# BaseTag.net
KiCad netlist of a schematic drawn in EAGLE
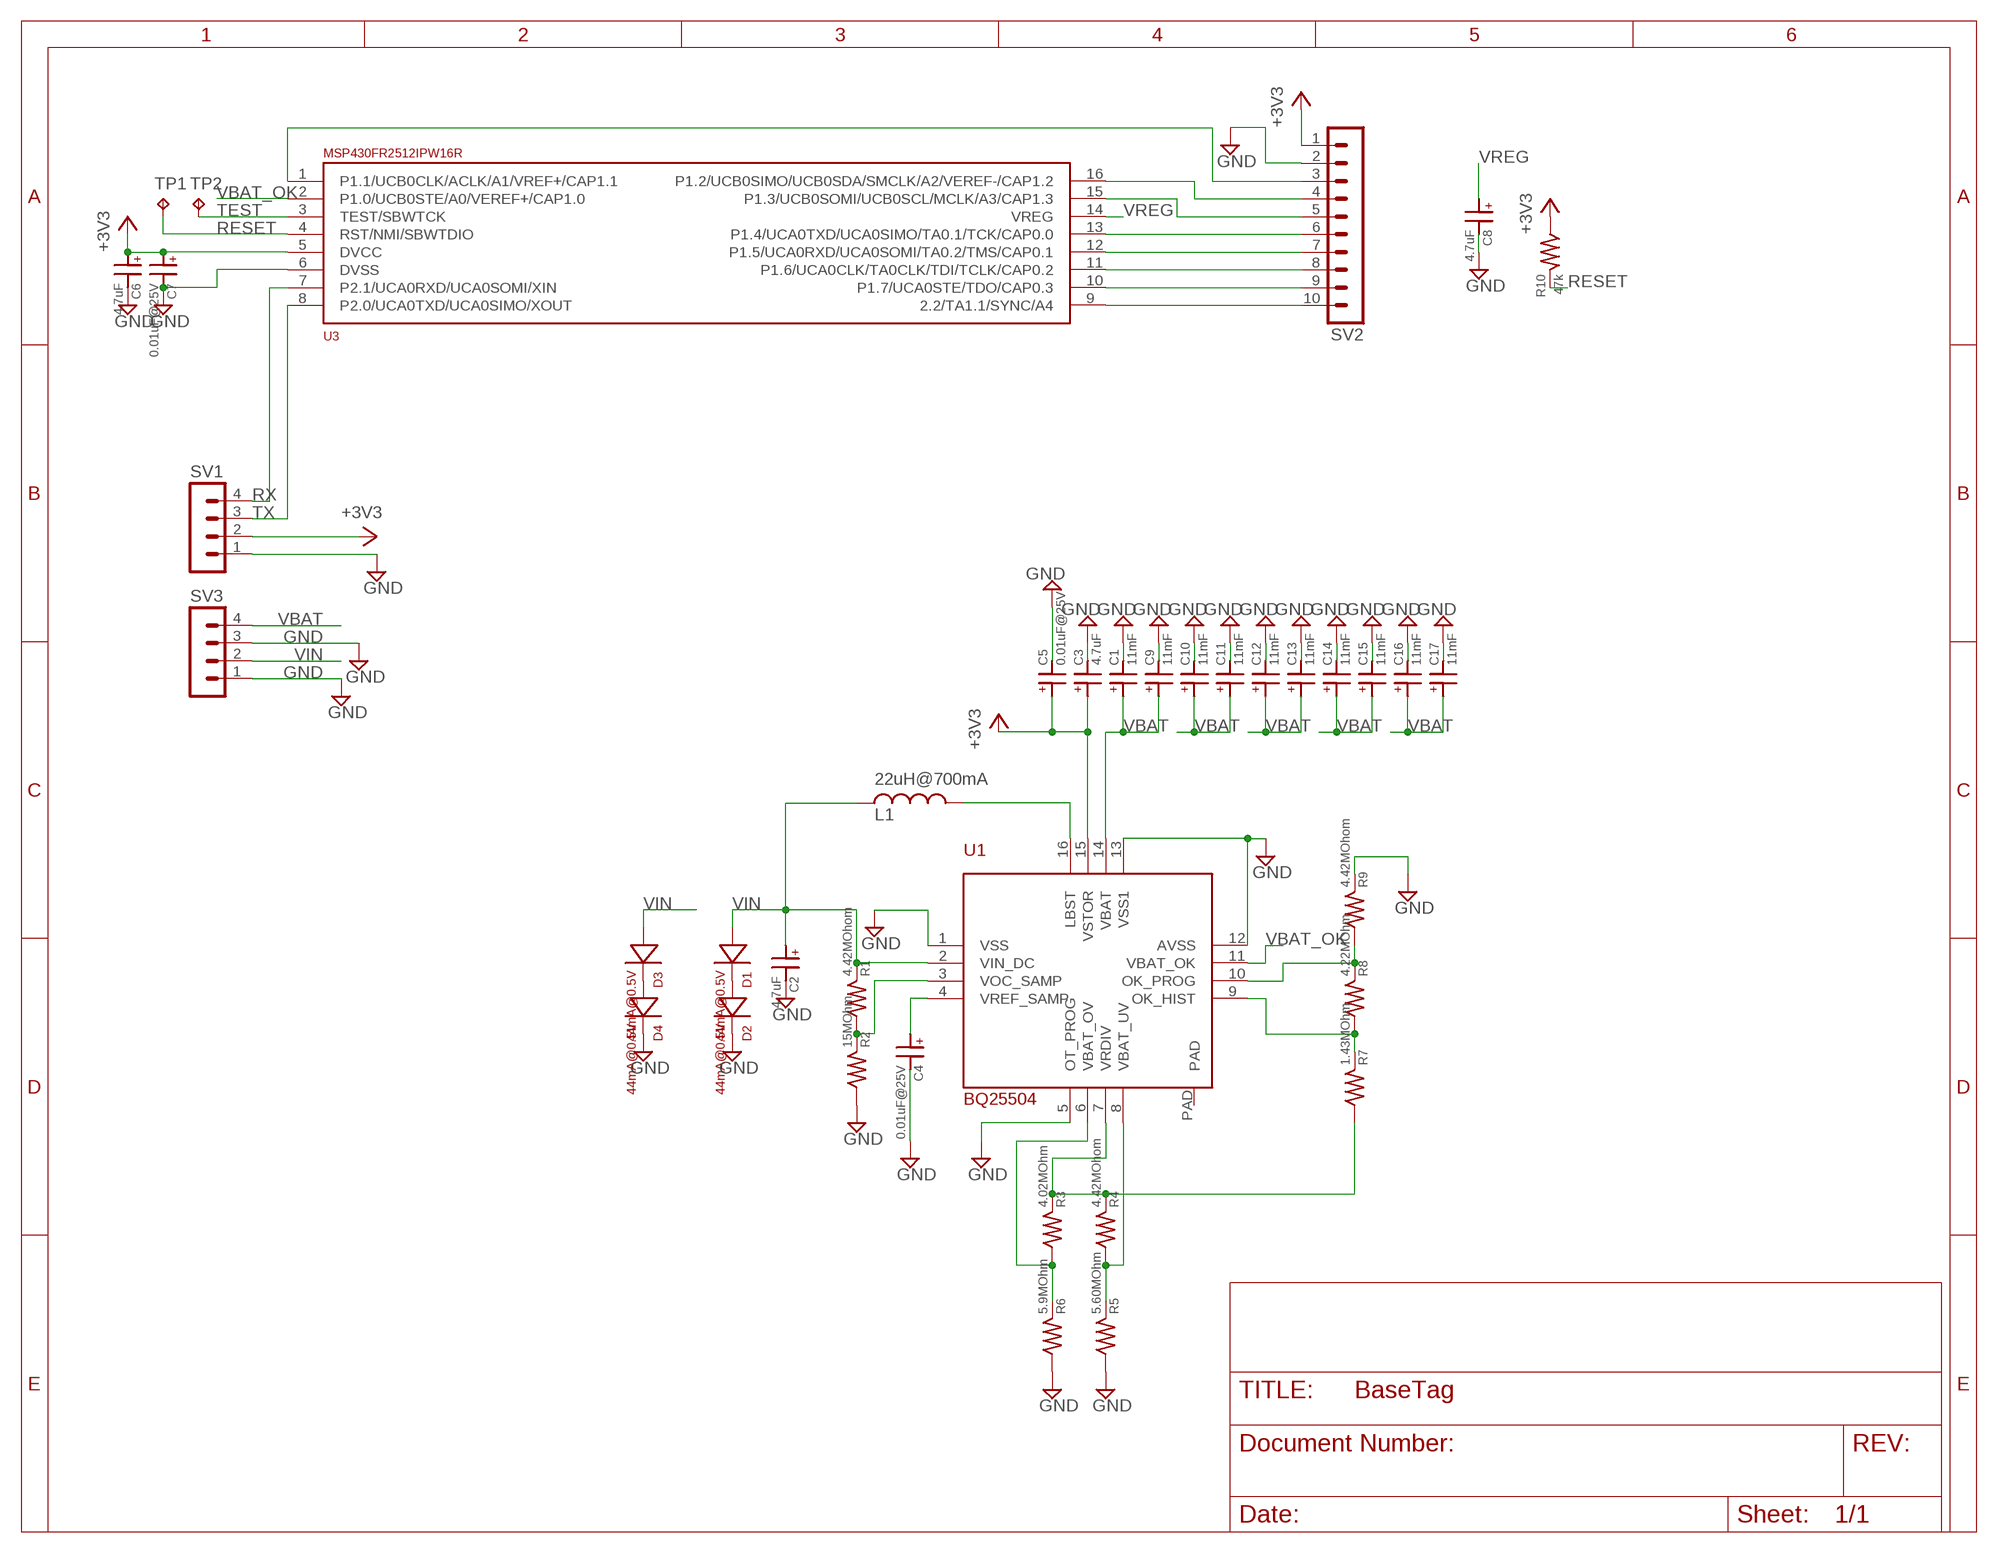
[diagram p0: schematic, sheet 1]

(export (version "E")
  (design (tool "Eeschema 10.0.6"))
  (components
    (comp (ref "C1")
      (value "11mF")
      (footprint "eagle-import:CPH3225A-2K")
      (fields (field (name "MFG") "Seiko Instruments ") (field (name "MPN") " CPH3225A-2K "))
      (libsource (lib "eagle-import") (part "Nelson-RLCD_4387371_C"))
    )
    (comp (ref "C2")
      (value "4.7uF")
      (footprint "eagle-import:0603")
      (fields (field (name "MFG") "Samsung") (field (name "MPN") "CL10A475MP5LNNC"))
      (libsource (lib "eagle-import") (part "C06034.7UF"))
    )
    (comp (ref "C3")
      (value "4.7uF")
      (footprint "eagle-import:0603")
      (fields (field (name "MFG") "Samsung") (field (name "MPN") "CL10A475MP5LNNC"))
      (libsource (lib "eagle-import") (part "Nelson-RLCD_4387371_C06034.7UF"))
    )
    (comp (ref "C4")
      (value "0.01uF@25V")
      (footprint "eagle-import:0603")
      (fields (field (name "MFG") "TDK") (field (name "MPN") "C1608C0G1E103J080AA"))
      (libsource (lib "eagle-import") (part "Nelson-RLCD_4387371_C06030.01UF"))
    )
    (comp (ref "C5")
      (value "0.01uF@25V")
      (footprint "eagle-import:0603")
      (fields (field (name "MFG") "TDK") (field (name "MPN") "C1608C0G1E103J080AA"))
      (libsource (lib "eagle-import") (part "Nelson-RLCD_4387371_C06030.01UF"))
    )
    (comp (ref "C6")
      (value "4.7uF")
      (footprint "eagle-import:0603")
      (fields (field (name "MFG") "Samsung") (field (name "MPN") "CL10A475MP5LNNC"))
      (libsource (lib "eagle-import") (part "Nelson-RLCD_4387371_C06034.7UF"))
    )
    (comp (ref "C7")
      (value "0.01uF@25V")
      (footprint "eagle-import:0603")
      (fields (field (name "MFG") "TDK") (field (name "MPN") "C1608C0G1E103J080AA"))
      (libsource (lib "eagle-import") (part "Nelson-RLCD_4387371_C06030.01UF"))
    )
    (comp (ref "C8")
      (value "4.7uF")
      (footprint "eagle-import:0603")
      (fields (field (name "MFG") "Samsung") (field (name "MPN") "CL10A475MP5LNNC"))
      (libsource (lib "eagle-import") (part "Nelson-RLCD_4387371_C06034.7UF"))
    )
    (comp (ref "C9")
      (value "11mF")
      (footprint "eagle-import:CPH3225A-2K")
      (fields (field (name "MFG") "Seiko Instruments ") (field (name "MPN") " CPH3225A-2K "))
      (libsource (lib "eagle-import") (part "Nelson-RLCD_4387371_C"))
    )
    (comp (ref "C10")
      (value "11mF")
      (footprint "eagle-import:CPH3225A-2K")
      (fields (field (name "MFG") "Seiko Instruments ") (field (name "MPN") " CPH3225A-2K "))
      (libsource (lib "eagle-import") (part "Nelson-RLCD_4387371_C"))
    )
    (comp (ref "C11")
      (value "11mF")
      (footprint "eagle-import:CPH3225A-2K")
      (fields (field (name "MFG") "Seiko Instruments ") (field (name "MPN") " CPH3225A-2K "))
      (libsource (lib "eagle-import") (part "C"))
    )
    (comp (ref "C12")
      (value "11mF")
      (footprint "eagle-import:CPH3225A-2K")
      (fields (field (name "MFG") "Seiko Instruments ") (field (name "MPN") " CPH3225A-2K "))
      (libsource (lib "eagle-import") (part "C"))
    )
    (comp (ref "C13")
      (value "11mF")
      (footprint "eagle-import:CPH3225A-2K")
      (fields (field (name "MFG") "Seiko Instruments ") (field (name "MPN") " CPH3225A-2K "))
      (libsource (lib "eagle-import") (part "C"))
    )
    (comp (ref "C14")
      (value "11mF")
      (footprint "eagle-import:CPH3225A-2K")
      (fields (field (name "MFG") "Seiko Instruments ") (field (name "MPN") " CPH3225A-2K "))
      (libsource (lib "eagle-import") (part "C"))
    )
    (comp (ref "C15")
      (value "11mF")
      (footprint "eagle-import:CPH3225A-2K")
      (fields (field (name "MFG") "Seiko Instruments ") (field (name "MPN") " CPH3225A-2K "))
      (libsource (lib "eagle-import") (part "C"))
    )
    (comp (ref "C16")
      (value "11mF")
      (footprint "eagle-import:CPH3225A-2K")
      (fields (field (name "MFG") "Seiko Instruments ") (field (name "MPN") " CPH3225A-2K "))
      (libsource (lib "eagle-import") (part "C"))
    )
    (comp (ref "C17")
      (value "11mF")
      (footprint "eagle-import:CPH3225A-2K")
      (fields (field (name "MFG") "Seiko Instruments ") (field (name "MPN") " CPH3225A-2K "))
      (libsource (lib "eagle-import") (part "C"))
    )
    (comp (ref "D1")
      (value "44mA@0.5V")
      (footprint "eagle-import:KXOB22-12X1F")
      (fields (field (name "MFG") "IXYS") (field (name "MPN") " KXOB22-12X1F "))
      (libsource (lib "eagle-import") (part "SOLAR-CELL"))
    )
    (comp (ref "D2")
      (value "44mA@0.5V")
      (footprint "eagle-import:KXOB22-12X1F")
      (fields (field (name "MFG") "IXYS") (field (name "MPN") " KXOB22-12X1F "))
      (libsource (lib "eagle-import") (part "SOLAR-CELL"))
    )
    (comp (ref "D3")
      (value "44mA@0.5V")
      (footprint "eagle-import:KXOB22-12X1F")
      (fields (field (name "MFG") "IXYS") (field (name "MPN") " KXOB22-12X1F "))
      (libsource (lib "eagle-import") (part "SOLAR-CELL"))
    )
    (comp (ref "D4")
      (value "44mA@0.5V")
      (footprint "eagle-import:KXOB22-12X1F")
      (fields (field (name "MFG") "IXYS") (field (name "MPN") " KXOB22-12X1F "))
      (libsource (lib "eagle-import") (part "SOLAR-CELL"))
    )
    (comp (ref "L1")
      (value "22uH@700mA")
      (footprint "eagle-import:LPS4018-223M")
      (fields (field (name "MFG") "coilcraft") (field (name "MPN") " LPS4018-223MRB "))
      (libsource (lib "eagle-import") (part "L22UH"))
    )
    (comp (ref "R1")
      (value "4.42MOhom")
      (footprint "eagle-import:0603")
      (fields (field (name "MFG") "Vishay") (field (name "MPN") "CRCW06034M42FKEA"))
      (libsource (lib "eagle-import") (part "R4.42M"))
    )
    (comp (ref "R2")
      (value "15MOhm")
      (footprint "eagle-import:0603")
      (fields (field (name "MFG") "Vishay") (field (name "MPN") "CRCW060315M0JPEAHR"))
      (libsource (lib "eagle-import") (part "R15M"))
    )
    (comp (ref "R3")
      (value "4.02MOhm")
      (footprint "eagle-import:0603")
      (fields (field (name "MFG") "Vishay") (field (name "MPN") "CRCW06034M02FKEA"))
      (libsource (lib "eagle-import") (part "R4.02M"))
    )
    (comp (ref "R4")
      (value "4.42MOhom")
      (footprint "eagle-import:0603")
      (fields (field (name "MFG") "Vishay") (field (name "MPN") "CRCW06034M42FKEA"))
      (libsource (lib "eagle-import") (part "R4.42M"))
    )
    (comp (ref "R5")
      (value "5.60MOhm")
      (footprint "eagle-import:0603")
      (fields (field (name "MFG") "Vishay") (field (name "MPN") "CRCW06035M60FKEA"))
      (libsource (lib "eagle-import") (part "R5.60"))
    )
    (comp (ref "R6")
      (value "5.9MOhm")
      (footprint "eagle-import:0603")
      (fields (field (name "MFG") "Vishay") (field (name "MPN") "CRCW06035M90FKEA"))
      (libsource (lib "eagle-import") (part "R5.9M"))
    )
    (comp (ref "R7")
      (value "1.43MOhm")
      (footprint "eagle-import:0603")
      (fields (field (name "MFG") "Vishay") (field (name "MPN") "CRCW06031M43FKEA"))
      (libsource (lib "eagle-import") (part "R1.43M"))
    )
    (comp (ref "R8")
      (value "4.22MOhm")
      (footprint "eagle-import:0603")
      (fields (field (name "MFG") "Vishay") (field (name "MPN") "CRCW06034M22FKEA"))
      (libsource (lib "eagle-import") (part "R4.22M"))
    )
    (comp (ref "R9")
      (value "4.42MOhom")
      (footprint "eagle-import:0603")
      (fields (field (name "MFG") "Vishay") (field (name "MPN") "CRCW06034M42FKEA"))
      (libsource (lib "eagle-import") (part "R4.42M"))
    )
    (comp (ref "R10")
      (value "47k")
      (footprint "eagle-import:0603")
      (fields (field (name "MFG") "Vishay") (field (name "MPN") "CRCW251247K0JNEG"))
      (libsource (lib "eagle-import") (part "R47K"))
    )
    (comp (ref "SV1")
      (value "MA04-1")
      (footprint "eagle-import:MA04-1")
      (libsource (lib "eagle-import") (part "MA04-1"))
    )
    (comp (ref "SV2")
      (value "MA10-1")
      (footprint "eagle-import:MA10-1")
      (libsource (lib "eagle-import") (part "MA10-1"))
    )
    (comp (ref "SV3")
      (value "MA04-1")
      (footprint "eagle-import:MA04-1")
      (libsource (lib "eagle-import") (part "MA04-1"))
    )
    (comp (ref "TP1")
      (value "TPB1,27")
      (footprint "eagle-import:B1,27")
      (libsource (lib "eagle-import") (part "TPB1,27"))
    )
    (comp (ref "TP2")
      (value "TPB1,27")
      (footprint "eagle-import:B1,27")
      (libsource (lib "eagle-import") (part "TPB1,27"))
    )
    (comp (ref "U1")
      (value "BQ25504")
      (footprint "eagle-import:VQFN-16")
      (fields (field (name "MFG") "TI"))
      (libsource (lib "eagle-import") (part "BQ25504"))
    )
    (comp (ref "U3")
      (value "MSP430FR2512IPW16RSOIC")
      (footprint "eagle-import:SOP65P640X120-16")
      (fields (field (name "MFG") "ti") (field (name "MPN") "  MSP430FR2512IPW16"))
      (libsource (lib "eagle-import") (part "MSP430FR2512IPW16RSOIC"))
    )
  )
  (nets
    (net (code "1") (name "+3V3") (class "Default")
      (node (ref "C3") (pin "+") (pinfunction "+_+") (pintype "bidirectional"))
      (node (ref "C5") (pin "+") (pinfunction "+_+") (pintype "bidirectional"))
      (node (ref "C6") (pin "+") (pinfunction "+_+") (pintype "bidirectional"))
      (node (ref "C7") (pin "+") (pinfunction "+_+") (pintype "bidirectional"))
      (node (ref "R10") (pin "+") (pinfunction "P$1_+") (pintype "bidirectional"))
      (node (ref "SV1") (pin "2") (pinfunction "2_2") (pintype "passive"))
      (node (ref "SV2") (pin "1") (pinfunction "1_1") (pintype "passive"))
      (node (ref "U1") (pin "15") (pinfunction "VSTOR_15") (pintype "bidirectional"))
      (node (ref "U3") (pin "5") (pinfunction "DVCC_5") (pintype "bidirectional"))
    )
    (net (code "2") (name "/RESET") (class "Default")
      (node (ref "R10") (pin "-") (pinfunction "P$2_-") (pintype "bidirectional"))
      (node (ref "TP1") (pin "TP") (pinfunction "TP_TP") (pintype "input"))
      (node (ref "U3") (pin "4") (pinfunction "RST/NMI/SBWTDIO_4") (pintype "bidirectional"))
    )
    (net (code "3") (name "/RX") (class "Default")
      (node (ref "SV1") (pin "4") (pinfunction "4_4") (pintype "passive"))
      (node (ref "U3") (pin "7") (pinfunction "P2.1/UCA0RXD/UCA0SOMI/XIN_7") (pintype "bidirectional"))
    )
    (net (code "4") (name "/TEST") (class "Default")
      (node (ref "TP2") (pin "TP") (pinfunction "TP_TP") (pintype "input"))
      (node (ref "U3") (pin "3") (pinfunction "TEST/SBWTCK_3") (pintype "bidirectional"))
    )
    (net (code "5") (name "/TX") (class "Default")
      (node (ref "SV1") (pin "3") (pinfunction "3_3") (pintype "passive"))
      (node (ref "U3") (pin "8") (pinfunction "P2.0/UCA0TXD/UCA0SIMO/XOUT_8") (pintype "bidirectional"))
    )
    (net (code "6") (name "/VBAT") (class "Default")
      (node (ref "C1") (pin "+") (pinfunction "+_+") (pintype "bidirectional"))
      (node (ref "C10") (pin "+") (pinfunction "+_+") (pintype "bidirectional"))
      (node (ref "C11") (pin "+") (pinfunction "+_+") (pintype "bidirectional"))
      (node (ref "C12") (pin "+") (pinfunction "+_+") (pintype "bidirectional"))
      (node (ref "C13") (pin "+") (pinfunction "+_+") (pintype "bidirectional"))
      (node (ref "C14") (pin "+") (pinfunction "+_+") (pintype "bidirectional"))
      (node (ref "C15") (pin "+") (pinfunction "+_+") (pintype "bidirectional"))
      (node (ref "C16") (pin "+") (pinfunction "+_+") (pintype "bidirectional"))
      (node (ref "C17") (pin "+") (pinfunction "+_+") (pintype "bidirectional"))
      (node (ref "C9") (pin "+") (pinfunction "+_+") (pintype "bidirectional"))
      (node (ref "SV3") (pin "4") (pinfunction "4_4") (pintype "passive"))
      (node (ref "U1") (pin "14") (pinfunction "VBAT_14") (pintype "bidirectional"))
    )
    (net (code "7") (name "/VBAT_OK") (class "Default")
      (node (ref "U1") (pin "11") (pinfunction "VBAT_OK_11") (pintype "bidirectional"))
      (node (ref "U3") (pin "2") (pinfunction "P1.0/UCB0STE/A0/VEREF+/CAP1.0_2") (pintype "bidirectional"))
    )
    (net (code "8") (name "/VIN") (class "Default")
      (node (ref "C2") (pin "+") (pinfunction "+_+") (pintype "bidirectional"))
      (node (ref "D1") (pin "+") (pinfunction "+_+") (pintype "bidirectional"))
      (node (ref "D3") (pin "+") (pinfunction "+_+") (pintype "bidirectional"))
      (node (ref "L1") (pin "P$1") (pinfunction "P$1_P$1") (pintype "bidirectional"))
      (node (ref "R1") (pin "-") (pinfunction "P$2_-") (pintype "bidirectional"))
      (node (ref "SV3") (pin "2") (pinfunction "2_2") (pintype "passive"))
      (node (ref "U1") (pin "2") (pinfunction "VIN_DC_2") (pintype "bidirectional"))
    )
    (net (code "9") (name "/VREG") (class "Default")
      (node (ref "C8") (pin "+") (pinfunction "+_+") (pintype "bidirectional"))
      (node (ref "U3") (pin "14") (pinfunction "VREG_14") (pintype "bidirectional"))
    )
    (net (code "10") (name "GND") (class "Default")
      (node (ref "C1") (pin "-") (pinfunction "-_-") (pintype "bidirectional"))
      (node (ref "C10") (pin "-") (pinfunction "-_-") (pintype "bidirectional"))
      (node (ref "C11") (pin "-") (pinfunction "-_-") (pintype "bidirectional"))
      (node (ref "C12") (pin "-") (pinfunction "-_-") (pintype "bidirectional"))
      (node (ref "C13") (pin "-") (pinfunction "-_-") (pintype "bidirectional"))
      (node (ref "C14") (pin "-") (pinfunction "-_-") (pintype "bidirectional"))
      (node (ref "C15") (pin "-") (pinfunction "-_-") (pintype "bidirectional"))
      (node (ref "C16") (pin "-") (pinfunction "-_-") (pintype "bidirectional"))
      (node (ref "C17") (pin "-") (pinfunction "-_-") (pintype "bidirectional"))
      (node (ref "C2") (pin "-") (pinfunction "-_-") (pintype "bidirectional"))
      (node (ref "C3") (pin "-") (pinfunction "-_-") (pintype "bidirectional"))
      (node (ref "C4") (pin "-") (pinfunction "-_-") (pintype "bidirectional"))
      (node (ref "C5") (pin "-") (pinfunction "-_-") (pintype "bidirectional"))
      (node (ref "C6") (pin "-") (pinfunction "-_-") (pintype "bidirectional"))
      (node (ref "C7") (pin "-") (pinfunction "-_-") (pintype "bidirectional"))
      (node (ref "C8") (pin "-") (pinfunction "-_-") (pintype "bidirectional"))
      (node (ref "C9") (pin "-") (pinfunction "-_-") (pintype "bidirectional"))
      (node (ref "D2") (pin "-") (pinfunction "-_-") (pintype "bidirectional"))
      (node (ref "D4") (pin "-") (pinfunction "-_-") (pintype "bidirectional"))
      (node (ref "R2") (pin "+") (pinfunction "P$1_+") (pintype "bidirectional"))
      (node (ref "R5") (pin "+") (pinfunction "P$1_+") (pintype "bidirectional"))
      (node (ref "R6") (pin "+") (pinfunction "P$1_+") (pintype "bidirectional"))
      (node (ref "R9") (pin "-") (pinfunction "P$2_-") (pintype "bidirectional"))
      (node (ref "SV1") (pin "1") (pinfunction "1_1") (pintype "passive"))
      (node (ref "SV2") (pin "2") (pinfunction "2_2") (pintype "passive"))
      (node (ref "SV3") (pin "1") (pinfunction "1_1") (pintype "passive"))
      (node (ref "SV3") (pin "3") (pinfunction "3_3") (pintype "passive"))
      (node (ref "U1") (pin "1") (pinfunction "VSS_1") (pintype "bidirectional"))
      (node (ref "U1") (pin "12") (pinfunction "AVSS_12") (pintype "bidirectional"))
      (node (ref "U1") (pin "13") (pinfunction "VSS1_13") (pintype "bidirectional"))
      (node (ref "U1") (pin "5") (pinfunction "OT_PROG_5") (pintype "bidirectional"))
      (node (ref "U3") (pin "6") (pinfunction "DVSS_6") (pintype "bidirectional"))
    )
    (net (code "11") (name "Net-(D1-Pad-)") (class "Default")
      (node (ref "D1") (pin "-") (pinfunction "-_-") (pintype "bidirectional"))
      (node (ref "D2") (pin "+") (pinfunction "+_+") (pintype "bidirectional"))
    )
    (net (code "12") (name "Net-(D3-Pad-)") (class "Default")
      (node (ref "D3") (pin "-") (pinfunction "-_-") (pintype "bidirectional"))
      (node (ref "D4") (pin "+") (pinfunction "+_+") (pintype "bidirectional"))
    )
    (net (code "13") (name "Net-(R1-P$1)") (class "Default")
      (node (ref "R1") (pin "+") (pinfunction "P$1_+") (pintype "bidirectional"))
      (node (ref "R2") (pin "-") (pinfunction "P$2_-") (pintype "bidirectional"))
      (node (ref "U1") (pin "3") (pinfunction "VOC_SAMP_3") (pintype "bidirectional"))
    )
    (net (code "14") (name "Net-(R3-P$1)") (class "Default")
      (node (ref "R3") (pin "+") (pinfunction "P$1_+") (pintype "bidirectional"))
      (node (ref "R6") (pin "-") (pinfunction "P$2_-") (pintype "bidirectional"))
      (node (ref "U1") (pin "6") (pinfunction "VBAT_OV_6") (pintype "bidirectional"))
    )
    (net (code "15") (name "Net-(R3-P$2)") (class "Default")
      (node (ref "R3") (pin "-") (pinfunction "P$2_-") (pintype "bidirectional"))
      (node (ref "R4") (pin "-") (pinfunction "P$2_-") (pintype "bidirectional"))
      (node (ref "R7") (pin "+") (pinfunction "P$1_+") (pintype "bidirectional"))
      (node (ref "U1") (pin "7") (pinfunction "VRDIV_7") (pintype "bidirectional"))
    )
    (net (code "16") (name "Net-(R4-P$1)") (class "Default")
      (node (ref "R4") (pin "+") (pinfunction "P$1_+") (pintype "bidirectional"))
      (node (ref "R5") (pin "-") (pinfunction "P$2_-") (pintype "bidirectional"))
      (node (ref "U1") (pin "8") (pinfunction "VBAT_UV_8") (pintype "bidirectional"))
    )
    (net (code "17") (name "Net-(R7-P$2)") (class "Default")
      (node (ref "R7") (pin "-") (pinfunction "P$2_-") (pintype "bidirectional"))
      (node (ref "R8") (pin "+") (pinfunction "P$1_+") (pintype "bidirectional"))
      (node (ref "U1") (pin "9") (pinfunction "OK_HIST_9") (pintype "bidirectional"))
    )
    (net (code "18") (name "Net-(R8-P$2)") (class "Default")
      (node (ref "R8") (pin "-") (pinfunction "P$2_-") (pintype "bidirectional"))
      (node (ref "R9") (pin "+") (pinfunction "P$1_+") (pintype "bidirectional"))
      (node (ref "U1") (pin "10") (pinfunction "OK_PROG_10") (pintype "bidirectional"))
    )
    (net (code "19") (name "Net-(U1-LBST)") (class "Default")
      (node (ref "L1") (pin "P$2") (pinfunction "P$2_P$2") (pintype "bidirectional"))
      (node (ref "U1") (pin "16") (pinfunction "LBST_16") (pintype "bidirectional"))
    )
    (net (code "20") (name "Net-(U1-VREF_SAMP)") (class "Default")
      (node (ref "C4") (pin "+") (pinfunction "+_+") (pintype "bidirectional"))
      (node (ref "U1") (pin "4") (pinfunction "VREF_SAMP_4") (pintype "bidirectional"))
    )
    (net (code "21") (name "Net-(U3-2.2{slash}TA1.1{slash}SYNC{slash}A4)") (class "Default")
      (node (ref "SV2") (pin "10") (pinfunction "10_10") (pintype "passive"))
      (node (ref "U3") (pin "9") (pinfunction "2.2/TA1.1/SYNC/A4_9") (pintype "bidirectional"))
    )
    (net (code "22") (name "Net-(U3-P1.1{slash}UCB0CLK{slash}ACLK{slash}A1{slash}VREF+{slash}CAP1.1)") (class "Default")
      (node (ref "SV2") (pin "3") (pinfunction "3_3") (pintype "passive"))
      (node (ref "U3") (pin "1") (pinfunction "P1.1/UCB0CLK/ACLK/A1/VREF+/CAP1.1_1") (pintype "bidirectional"))
    )
    (net (code "23") (name "Net-(U3-P1.2{slash}UCB0SIMO{slash}UCB0SDA{slash}SMCLK{slash}A2{slash}VEREF-{slash}CAP1.2)") (class "Default")
      (node (ref "SV2") (pin "4") (pinfunction "4_4") (pintype "passive"))
      (node (ref "U3") (pin "16") (pinfunction "P1.2/UCB0SIMO/UCB0SDA/SMCLK/A2/VEREF-/CAP1.2_16") (pintype "bidirectional"))
    )
    (net (code "24") (name "Net-(U3-P1.3{slash}UCB0SOMI{slash}UCB0SCL{slash}MCLK{slash}A3{slash}CAP1.3)") (class "Default")
      (node (ref "SV2") (pin "5") (pinfunction "5_5") (pintype "passive"))
      (node (ref "U3") (pin "15") (pinfunction "P1.3/UCB0SOMI/UCB0SCL/MCLK/A3/CAP1.3_15") (pintype "bidirectional"))
    )
    (net (code "25") (name "Net-(U3-P1.4{slash}UCA0TXD{slash}UCA0SIMO{slash}TA0.1{slash}TCK{slash}CAP0.0)") (class "Default")
      (node (ref "SV2") (pin "6") (pinfunction "6_6") (pintype "passive"))
      (node (ref "U3") (pin "13") (pinfunction "P1.4/UCA0TXD/UCA0SIMO/TA0.1/TCK/CAP0.0_13") (pintype "bidirectional"))
    )
    (net (code "26") (name "Net-(U3-P1.5{slash}UCA0RXD{slash}UCA0SOMI{slash}TA0.2{slash}TMS{slash}CAP0.1)") (class "Default")
      (node (ref "SV2") (pin "7") (pinfunction "7_7") (pintype "passive"))
      (node (ref "U3") (pin "12") (pinfunction "P1.5/UCA0RXD/UCA0SOMI/TA0.2/TMS/CAP0.1_12") (pintype "bidirectional"))
    )
    (net (code "27") (name "Net-(U3-P1.6{slash}UCA0CLK{slash}TA0CLK{slash}TDI{slash}TCLK{slash}CAP0.2)") (class "Default")
      (node (ref "SV2") (pin "8") (pinfunction "8_8") (pintype "passive"))
      (node (ref "U3") (pin "11") (pinfunction "P1.6/UCA0CLK/TA0CLK/TDI/TCLK/CAP0.2_11") (pintype "bidirectional"))
    )
    (net (code "28") (name "Net-(U3-P1.7{slash}UCA0STE{slash}TDO{slash}CAP0.3)") (class "Default")
      (node (ref "SV2") (pin "9") (pinfunction "9_9") (pintype "passive"))
      (node (ref "U3") (pin "10") (pinfunction "P1.7/UCA0STE/TDO/CAP0.3_10") (pintype "bidirectional"))
    )
    (net (code "29") (name "unconnected-(U1-PadPAD)") (class "Default")
      (node (ref "U1") (pin "PAD") (pinfunction "PAD_PAD") (pintype "bidirectional"))
    )
  )
)
